# ADS124S08-Dev-Board.net
KiCad netlist of a schematic drawn in EAGLE
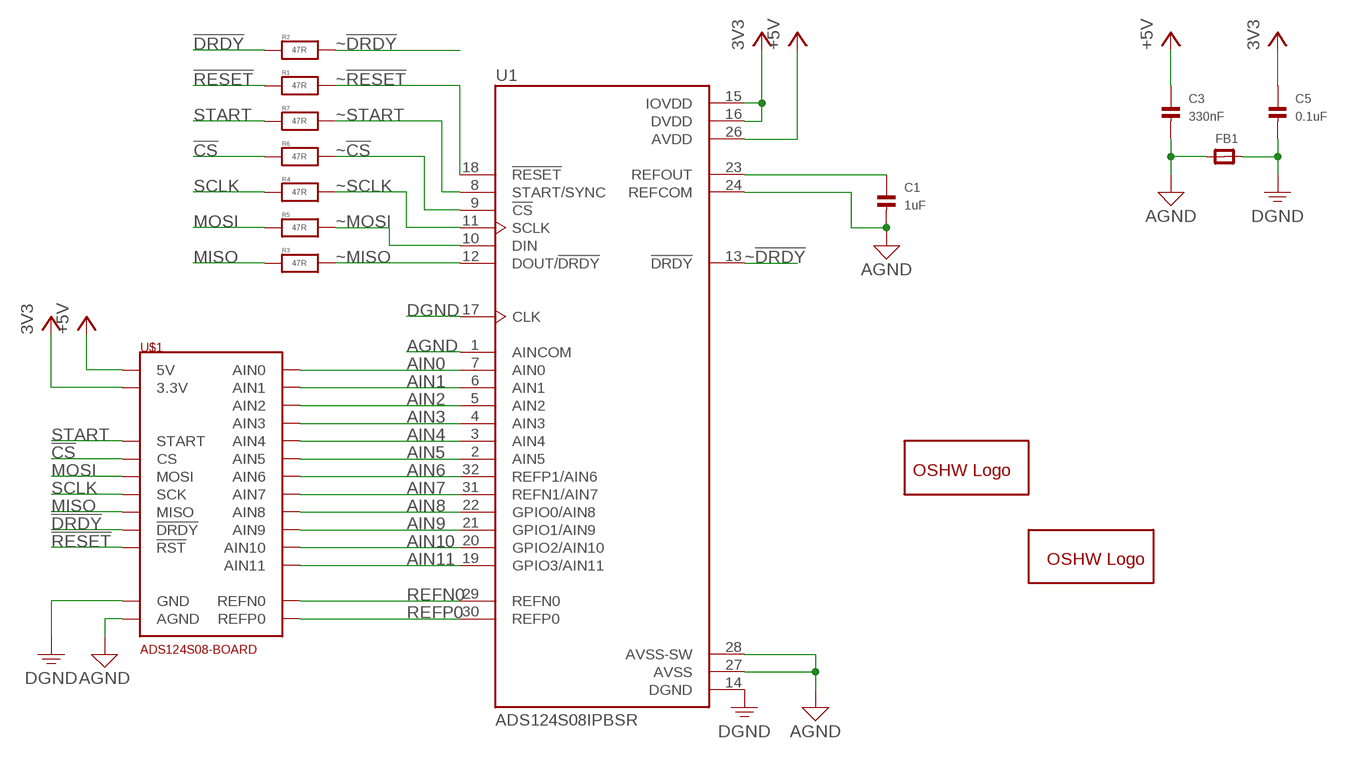
[diagram p0: schematic, sheet 1]

(export (version "E")
  (design (tool "Eeschema 10.0.6"))
  (components
    (comp (ref "C1")
      (value "1uF")
      (footprint "eagle-import:C0603-MINI")
      (fields (field (name "MF") "AVX") (field (name "MPN") "08055C104JAT2A"))
      (libsource (lib "eagle-import") (part "CAP_CERAMIC0603MINI"))
    )
    (comp (ref "C3")
      (value "330nF")
      (footprint "eagle-import:C0603-MINI")
      (fields (field (name "MF") "AVX") (field (name "MPN") "08055C104JAT2A"))
      (libsource (lib "eagle-import") (part "CAP_CERAMIC0603MINI"))
    )
    (comp (ref "C5")
      (value "0.1uF")
      (footprint "eagle-import:C0603-MINI")
      (fields (field (name "MF") "AVX") (field (name "MPN") "08055C104JAT2A"))
      (libsource (lib "eagle-import") (part "CAP_CERAMIC0603MINI"))
    )
    (comp (ref "FB1")
      (value "FERRITE_0603")
      (footprint "eagle-import:_0603")
      (libsource (lib "eagle-import") (part "FERRITE_0603"))
    )
    (comp (ref "GOLD_ORB_SM1")
      (value "OSHWLOGOLOGO5MM")
      (footprint "eagle-import:OSHW_5MM")
      (libsource (lib "eagle-import") (part "OSHWLOGOLOGO5MM"))
    )
    (comp (ref "GOLD_ORB_SM2")
      (value "OSHWLOGOLOGO8MM")
      (footprint "eagle-import:OSHW_8MM")
      (libsource (lib "eagle-import") (part "OSHWLOGOLOGO8MM"))
    )
    (comp (ref "R1")
      (value "47R")
      (footprint "eagle-import:R0603-MINI")
      (libsource (lib "eagle-import") (part "RESISTOR0603MINI"))
    )
    (comp (ref "R2")
      (value "47R")
      (footprint "eagle-import:R0603-MINI")
      (libsource (lib "eagle-import") (part "RESISTOR0603MINI"))
    )
    (comp (ref "R3")
      (value "47R")
      (footprint "eagle-import:R0603-MINI")
      (libsource (lib "eagle-import") (part "RESISTOR0603MINI"))
    )
    (comp (ref "R4")
      (value "47R")
      (footprint "eagle-import:R0603-MINI")
      (libsource (lib "eagle-import") (part "RESISTOR0603MINI"))
    )
    (comp (ref "R5")
      (value "47R")
      (footprint "eagle-import:R0603-MINI")
      (libsource (lib "eagle-import") (part "RESISTOR0603MINI"))
    )
    (comp (ref "R6")
      (value "47R")
      (footprint "eagle-import:R0603-MINI")
      (libsource (lib "eagle-import") (part "RESISTOR0603MINI"))
    )
    (comp (ref "R7")
      (value "47R")
      (footprint "eagle-import:R0603-MINI")
      (libsource (lib "eagle-import") (part "RESISTOR0603MINI"))
    )
    (comp (ref "U$1")
      (value "ADS124S08-BOARD")
      (footprint "eagle-import:ADS124S08-BOARD")
      (libsource (lib "eagle-import") (part "ADS124S08-BOARD"))
    )
    (comp (ref "U1")
      (value "ADS124S08IPBSR")
      (footprint "eagle-import:QFP50P700X700X120-32N")
      (fields (field (name "MF") "Texas Instruments"))
      (libsource (lib "eagle-import") (part "ADS124S08IPBSR"))
    )
  )
  (nets
    (net (code "1") (name "+5V") (class "Default")
      (node (ref "C3") (pin "1") (pinfunction "P$1_1") (pintype "passive"))
      (node (ref "U$1") (pin "14") (pinfunction "5V_14") (pintype "bidirectional"))
      (node (ref "U1") (pin "26") (pinfunction "AVDD_26") (pintype "power_in"))
    )
    (net (code "2") (name "/AIN0") (class "Default")
      (node (ref "U$1") (pin "12") (pinfunction "AIN0_12") (pintype "bidirectional"))
      (node (ref "U1") (pin "7") (pinfunction "AIN0_7") (pintype "input"))
    )
    (net (code "3") (name "/AIN1") (class "Default")
      (node (ref "U$1") (pin "11") (pinfunction "AIN1_11") (pintype "bidirectional"))
      (node (ref "U1") (pin "6") (pinfunction "AIN1_6") (pintype "input"))
    )
    (net (code "4") (name "/AIN2") (class "Default")
      (node (ref "U$1") (pin "10") (pinfunction "AIN2_10") (pintype "bidirectional"))
      (node (ref "U1") (pin "5") (pinfunction "AIN2_5") (pintype "input"))
    )
    (net (code "5") (name "/AIN3") (class "Default")
      (node (ref "U$1") (pin "9") (pinfunction "AIN3_9") (pintype "bidirectional"))
      (node (ref "U1") (pin "4") (pinfunction "AIN3_4") (pintype "input"))
    )
    (net (code "6") (name "/AIN4") (class "Default")
      (node (ref "U$1") (pin "8") (pinfunction "AIN4_8") (pintype "bidirectional"))
      (node (ref "U1") (pin "3") (pinfunction "AIN4_3") (pintype "input"))
    )
    (net (code "7") (name "/AIN5") (class "Default")
      (node (ref "U$1") (pin "7") (pinfunction "AIN5_7") (pintype "bidirectional"))
      (node (ref "U1") (pin "2") (pinfunction "AIN5_2") (pintype "input"))
    )
    (net (code "8") (name "/AIN6") (class "Default")
      (node (ref "U$1") (pin "6") (pinfunction "AIN6_6") (pintype "bidirectional"))
      (node (ref "U1") (pin "32") (pinfunction "REFP1/AIN6_32") (pintype "input"))
    )
    (net (code "9") (name "/AIN7") (class "Default")
      (node (ref "U$1") (pin "5") (pinfunction "AIN7_5") (pintype "bidirectional"))
      (node (ref "U1") (pin "31") (pinfunction "REFN1/AIN7_31") (pintype "input"))
    )
    (net (code "10") (name "/AIN8") (class "Default")
      (node (ref "U$1") (pin "4") (pinfunction "AIN8_4") (pintype "bidirectional"))
      (node (ref "U1") (pin "22") (pinfunction "GPIO0/AIN8_22") (pintype "bidirectional"))
    )
    (net (code "11") (name "/AIN9") (class "Default")
      (node (ref "U$1") (pin "3") (pinfunction "AIN9_3") (pintype "bidirectional"))
      (node (ref "U1") (pin "21") (pinfunction "GPIO1/AIN9_21") (pintype "bidirectional"))
    )
    (net (code "12") (name "/AIN10") (class "Default")
      (node (ref "U$1") (pin "2") (pinfunction "AIN10_2") (pintype "bidirectional"))
      (node (ref "U1") (pin "20") (pinfunction "GPIO2/AIN10_20") (pintype "bidirectional"))
    )
    (net (code "13") (name "/AIN11") (class "Default")
      (node (ref "U$1") (pin "1") (pinfunction "AIN11_1") (pintype "bidirectional"))
      (node (ref "U1") (pin "19") (pinfunction "GPIO3/AIN11_19") (pintype "bidirectional"))
    )
    (net (code "14") (name "/MISO") (class "Default")
      (node (ref "R3") (pin "1") (pinfunction "1_1") (pintype "passive"))
      (node (ref "U$1") (pin "18") (pinfunction "MISO_18") (pintype "bidirectional"))
    )
    (net (code "15") (name "/MOSI") (class "Default")
      (node (ref "R5") (pin "1") (pinfunction "1_1") (pintype "passive"))
      (node (ref "U$1") (pin "20") (pinfunction "MOSI_20") (pintype "bidirectional"))
    )
    (net (code "16") (name "/REFN0") (class "Default")
      (node (ref "U$1") (pin "23") (pinfunction "REFN0_23") (pintype "bidirectional"))
      (node (ref "U1") (pin "29") (pinfunction "REFN0_29") (pintype "input"))
    )
    (net (code "17") (name "/REFP0") (class "Default")
      (node (ref "U$1") (pin "24") (pinfunction "REFP0_24") (pintype "bidirectional"))
      (node (ref "U1") (pin "30") (pinfunction "REFP0_30") (pintype "input"))
    )
    (net (code "18") (name "/SCLK") (class "Default")
      (node (ref "R4") (pin "1") (pinfunction "1_1") (pintype "passive"))
      (node (ref "U$1") (pin "19") (pinfunction "SCK_19") (pintype "bidirectional"))
    )
    (net (code "19") (name "/START") (class "Default")
      (node (ref "R7") (pin "1") (pinfunction "1_1") (pintype "passive"))
      (node (ref "U$1") (pin "22") (pinfunction "START_22") (pintype "bidirectional"))
    )
    (net (code "20") (name "/~CS") (class "Default")
      (node (ref "R6") (pin "2") (pinfunction "2_2") (pintype "passive"))
      (node (ref "U1") (pin "9") (pinfunction "~{CS}_9") (pintype "input"))
    )
    (net (code "21") (name "/~DRDY") (class "Default")
      (node (ref "R2") (pin "2") (pinfunction "2_2") (pintype "passive"))
      (node (ref "U1") (pin "13") (pinfunction "~{DRDY}_13") (pintype "output"))
    )
    (net (code "22") (name "/~RESET") (class "Default")
      (node (ref "R1") (pin "2") (pinfunction "2_2") (pintype "passive"))
      (node (ref "U1") (pin "18") (pinfunction "~{RESET}_18") (pintype "input"))
    )
    (net (code "23") (name "/~{CS}") (class "Default")
      (node (ref "R6") (pin "1") (pinfunction "1_1") (pintype "passive"))
      (node (ref "U$1") (pin "21") (pinfunction "CS_21") (pintype "bidirectional"))
    )
    (net (code "24") (name "/~{DRDY}") (class "Default")
      (node (ref "R2") (pin "1") (pinfunction "1_1") (pintype "passive"))
      (node (ref "U$1") (pin "17") (pinfunction "~{DRDY}_17") (pintype "bidirectional"))
    )
    (net (code "25") (name "/~{MISO}") (class "Default")
      (node (ref "R3") (pin "2") (pinfunction "2_2") (pintype "passive"))
      (node (ref "U1") (pin "12") (pinfunction "DOUT/~{DRDY}_12") (pintype "output"))
    )
    (net (code "26") (name "/~{MOSI}") (class "Default")
      (node (ref "R5") (pin "2") (pinfunction "2_2") (pintype "passive"))
      (node (ref "U1") (pin "10") (pinfunction "DIN_10") (pintype "input"))
    )
    (net (code "27") (name "/~{RESET}") (class "Default")
      (node (ref "R1") (pin "1") (pinfunction "1_1") (pintype "passive"))
      (node (ref "U$1") (pin "16") (pinfunction "~{RST}_16") (pintype "bidirectional"))
    )
    (net (code "28") (name "/~{SCLK}") (class "Default")
      (node (ref "R4") (pin "2") (pinfunction "2_2") (pintype "passive"))
      (node (ref "U1") (pin "11") (pinfunction "SCLK_11") (pintype "input"))
    )
    (net (code "29") (name "/~{START}") (class "Default")
      (node (ref "R7") (pin "2") (pinfunction "2_2") (pintype "passive"))
      (node (ref "U1") (pin "8") (pinfunction "START/SYNC_8") (pintype "input"))
    )
    (net (code "30") (name "3V3") (class "Default")
      (node (ref "C5") (pin "1") (pinfunction "P$1_1") (pintype "passive"))
      (node (ref "U$1") (pin "15") (pinfunction "3.3V_15") (pintype "bidirectional"))
      (node (ref "U1") (pin "15") (pinfunction "IOVDD_15") (pintype "power_in"))
      (node (ref "U1") (pin "16") (pinfunction "DVDD_16") (pintype "power_in"))
    )
    (net (code "31") (name "AGND") (class "Default")
      (node (ref "C1") (pin "2") (pinfunction "P$2_2") (pintype "passive"))
      (node (ref "C3") (pin "2") (pinfunction "P$2_2") (pintype "passive"))
      (node (ref "FB1") (pin "1") (pinfunction "P$1_1") (pintype "passive"))
      (node (ref "U$1") (pin "25") (pinfunction "AGND_25") (pintype "bidirectional"))
      (node (ref "U1") (pin "1") (pinfunction "AINCOM_1") (pintype "input"))
      (node (ref "U1") (pin "24") (pinfunction "REFCOM_24") (pintype "output"))
      (node (ref "U1") (pin "27") (pinfunction "AVSS_27") (pintype "power_in"))
      (node (ref "U1") (pin "28") (pinfunction "AVSS-SW_28") (pintype "power_in"))
    )
    (net (code "32") (name "DGND") (class "Default")
      (node (ref "C5") (pin "2") (pinfunction "P$2_2") (pintype "passive"))
      (node (ref "FB1") (pin "2") (pinfunction "P$2_2") (pintype "passive"))
      (node (ref "U$1") (pin "13") (pinfunction "GND_13") (pintype "bidirectional"))
      (node (ref "U$1") (pin "26") (pinfunction "GND_26") (pintype "bidirectional"))
      (node (ref "U1") (pin "14") (pinfunction "DGND_14") (pintype "power_in"))
      (node (ref "U1") (pin "17") (pinfunction "CLK_17") (pintype "input"))
    )
    (net (code "33") (name "Net-(C1-P$1)") (class "Default")
      (node (ref "C1") (pin "1") (pinfunction "P$1_1") (pintype "passive"))
      (node (ref "U1") (pin "23") (pinfunction "REFOUT_23") (pintype "output"))
    )
  )
)
